# STUSB4500_PS.net
KiCad netlist of a schematic drawn in EAGLE
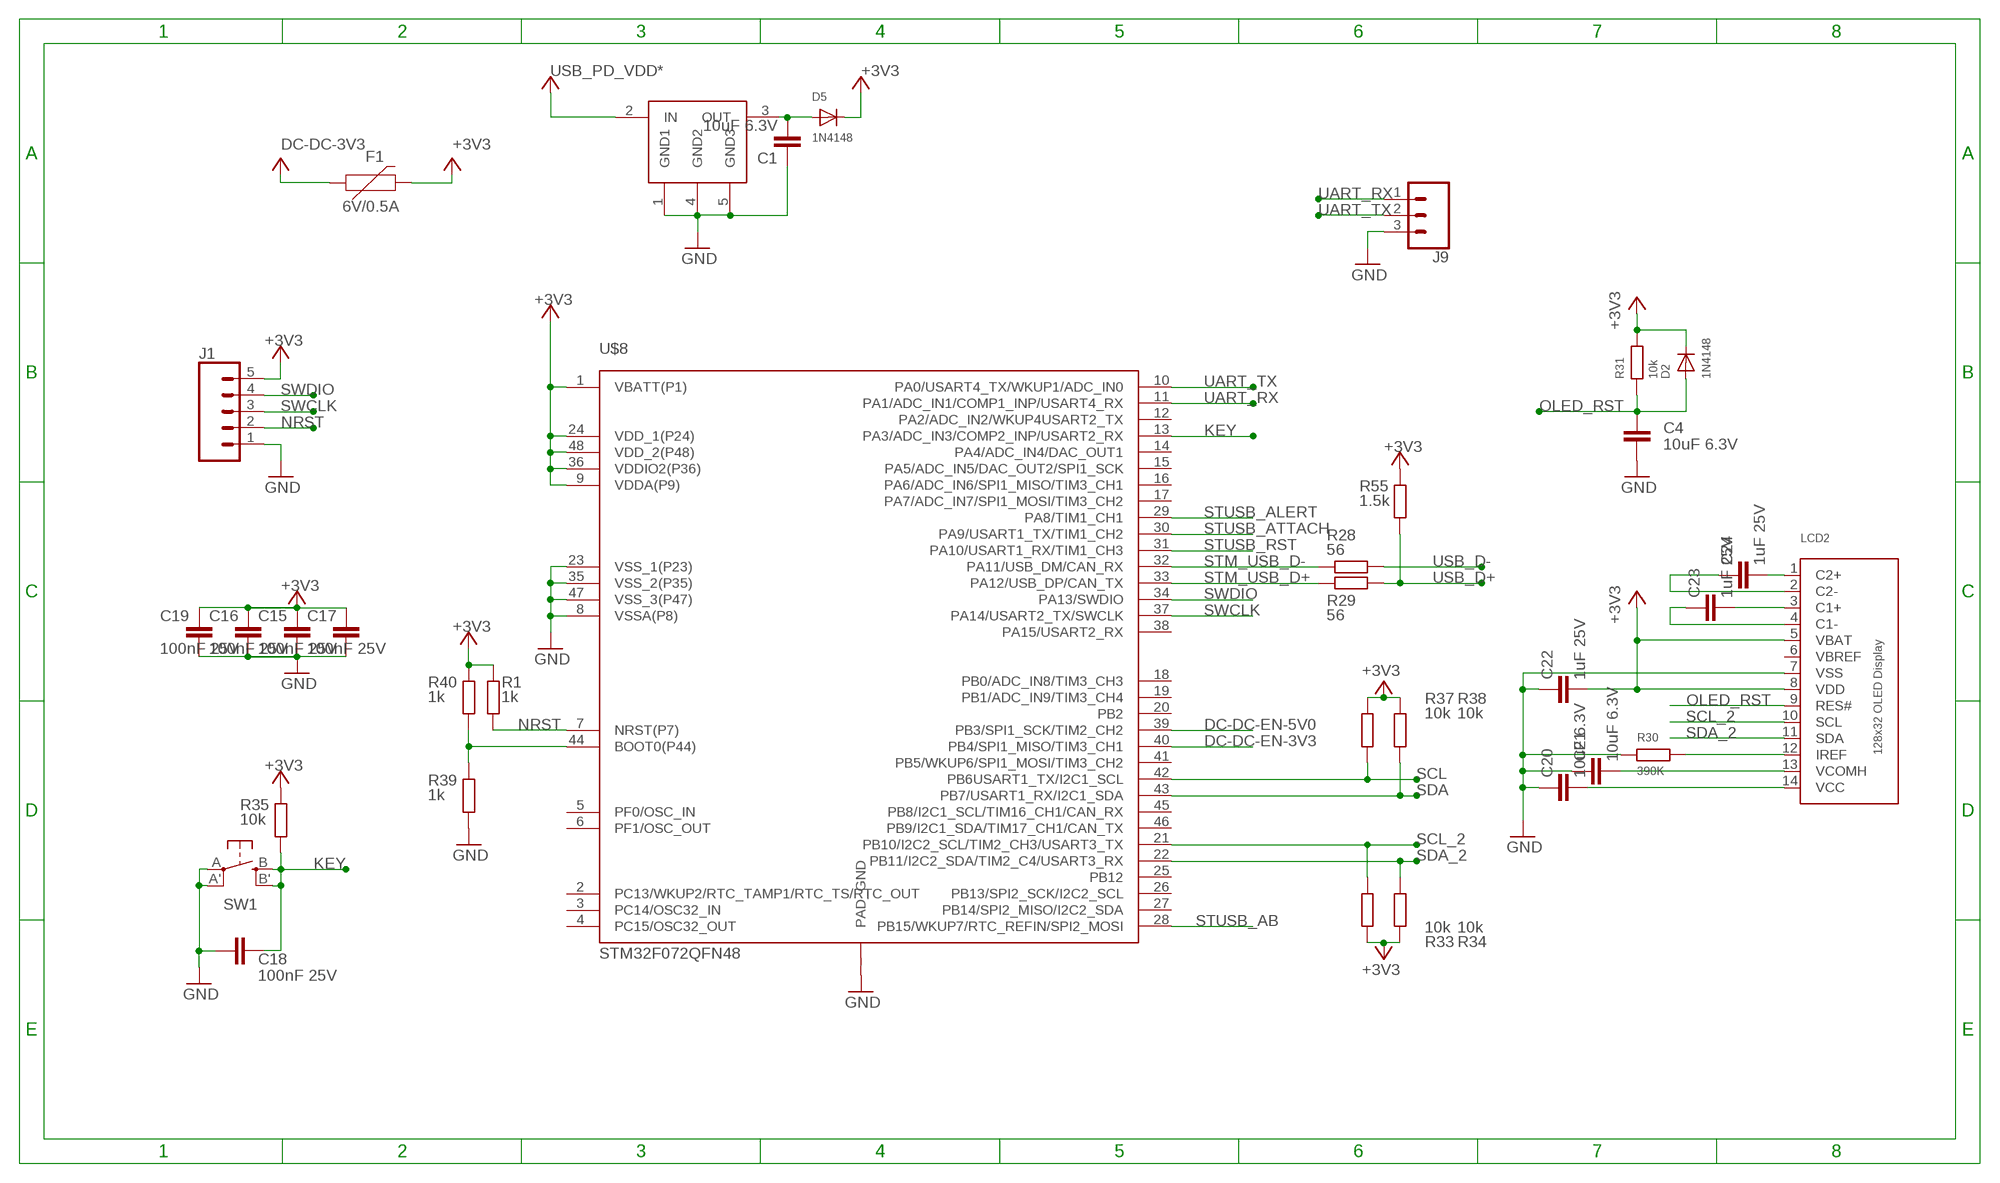
[diagram p0: schematic, sheet 1]
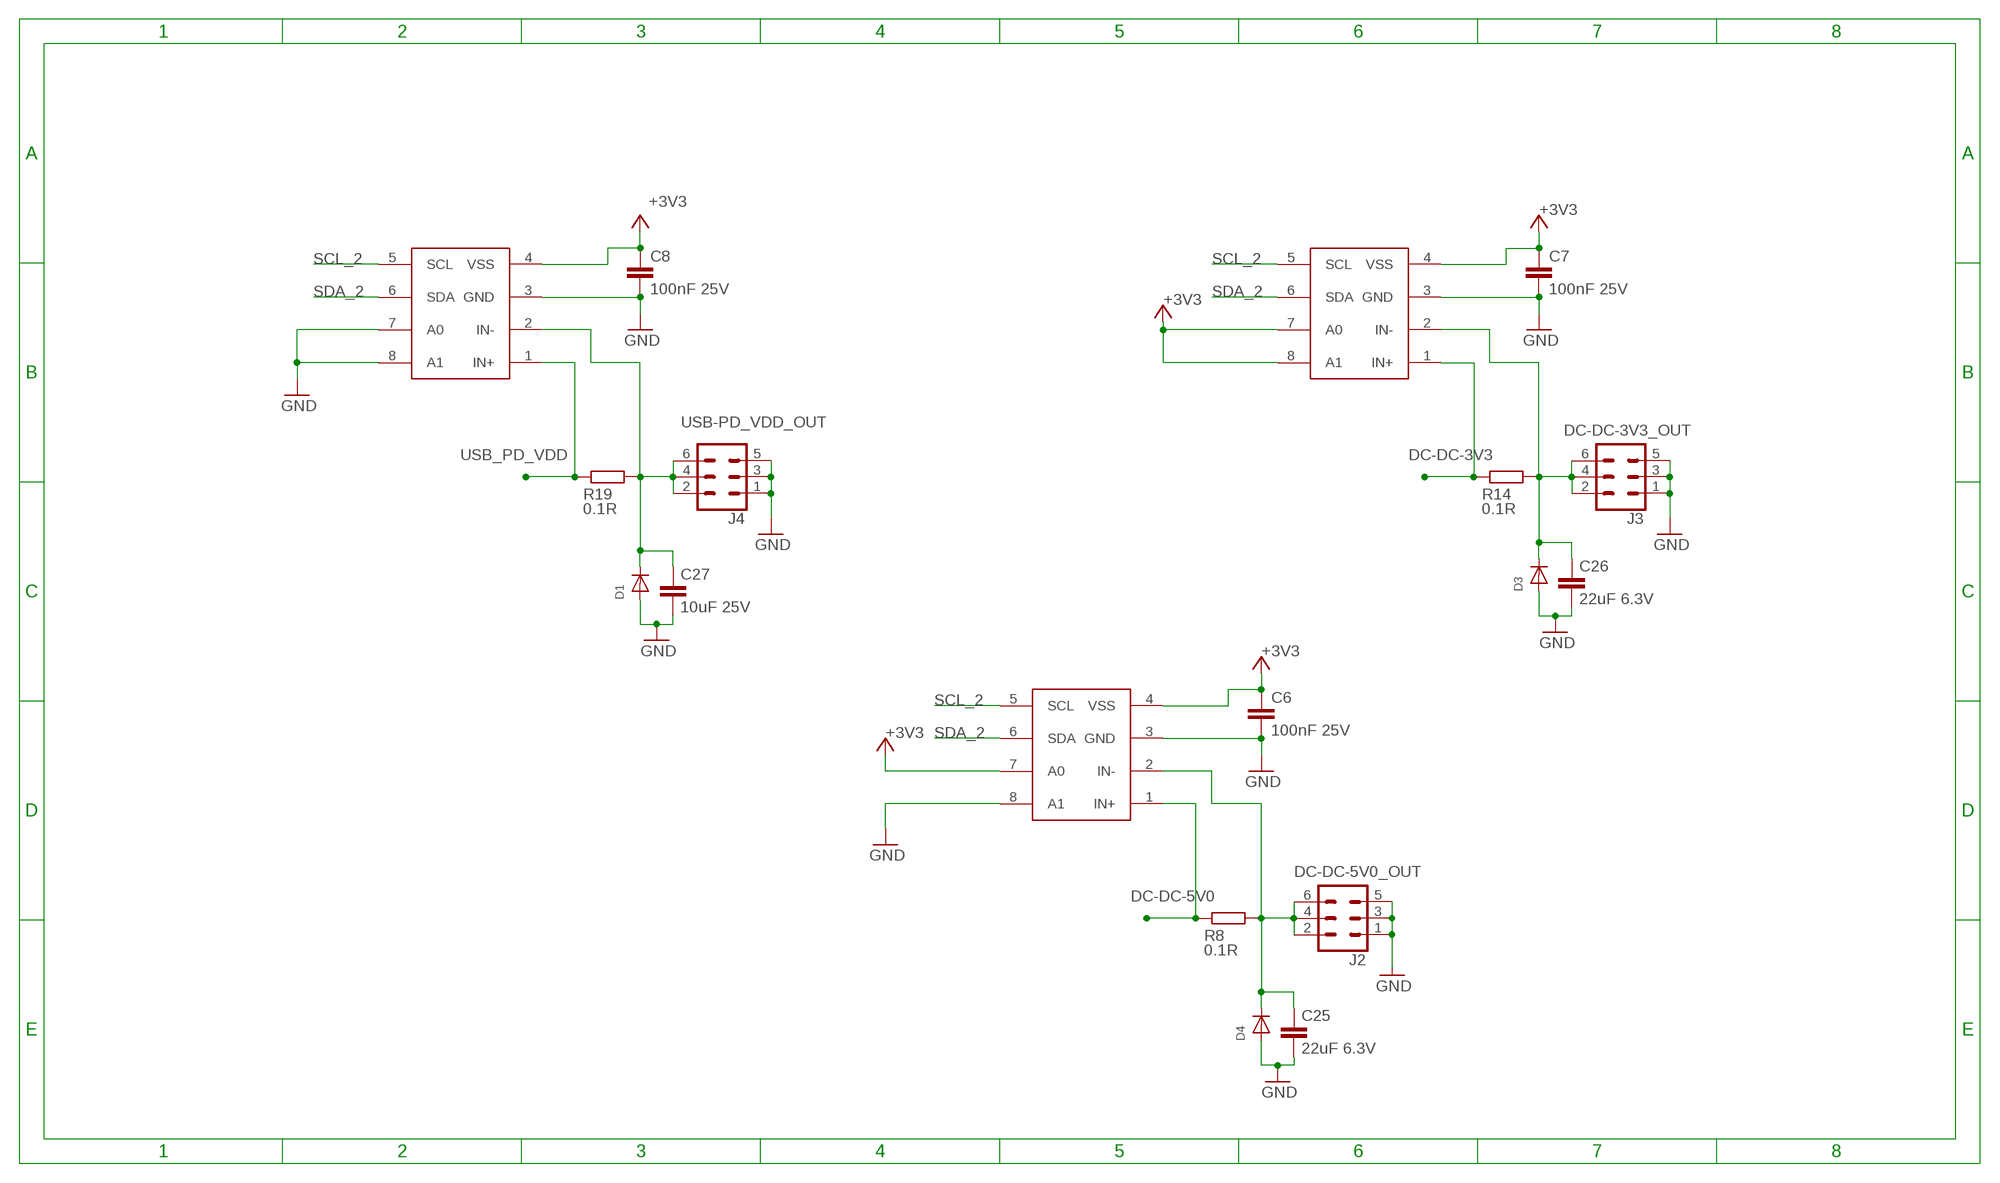
[diagram p1: schematic, sheet 2]
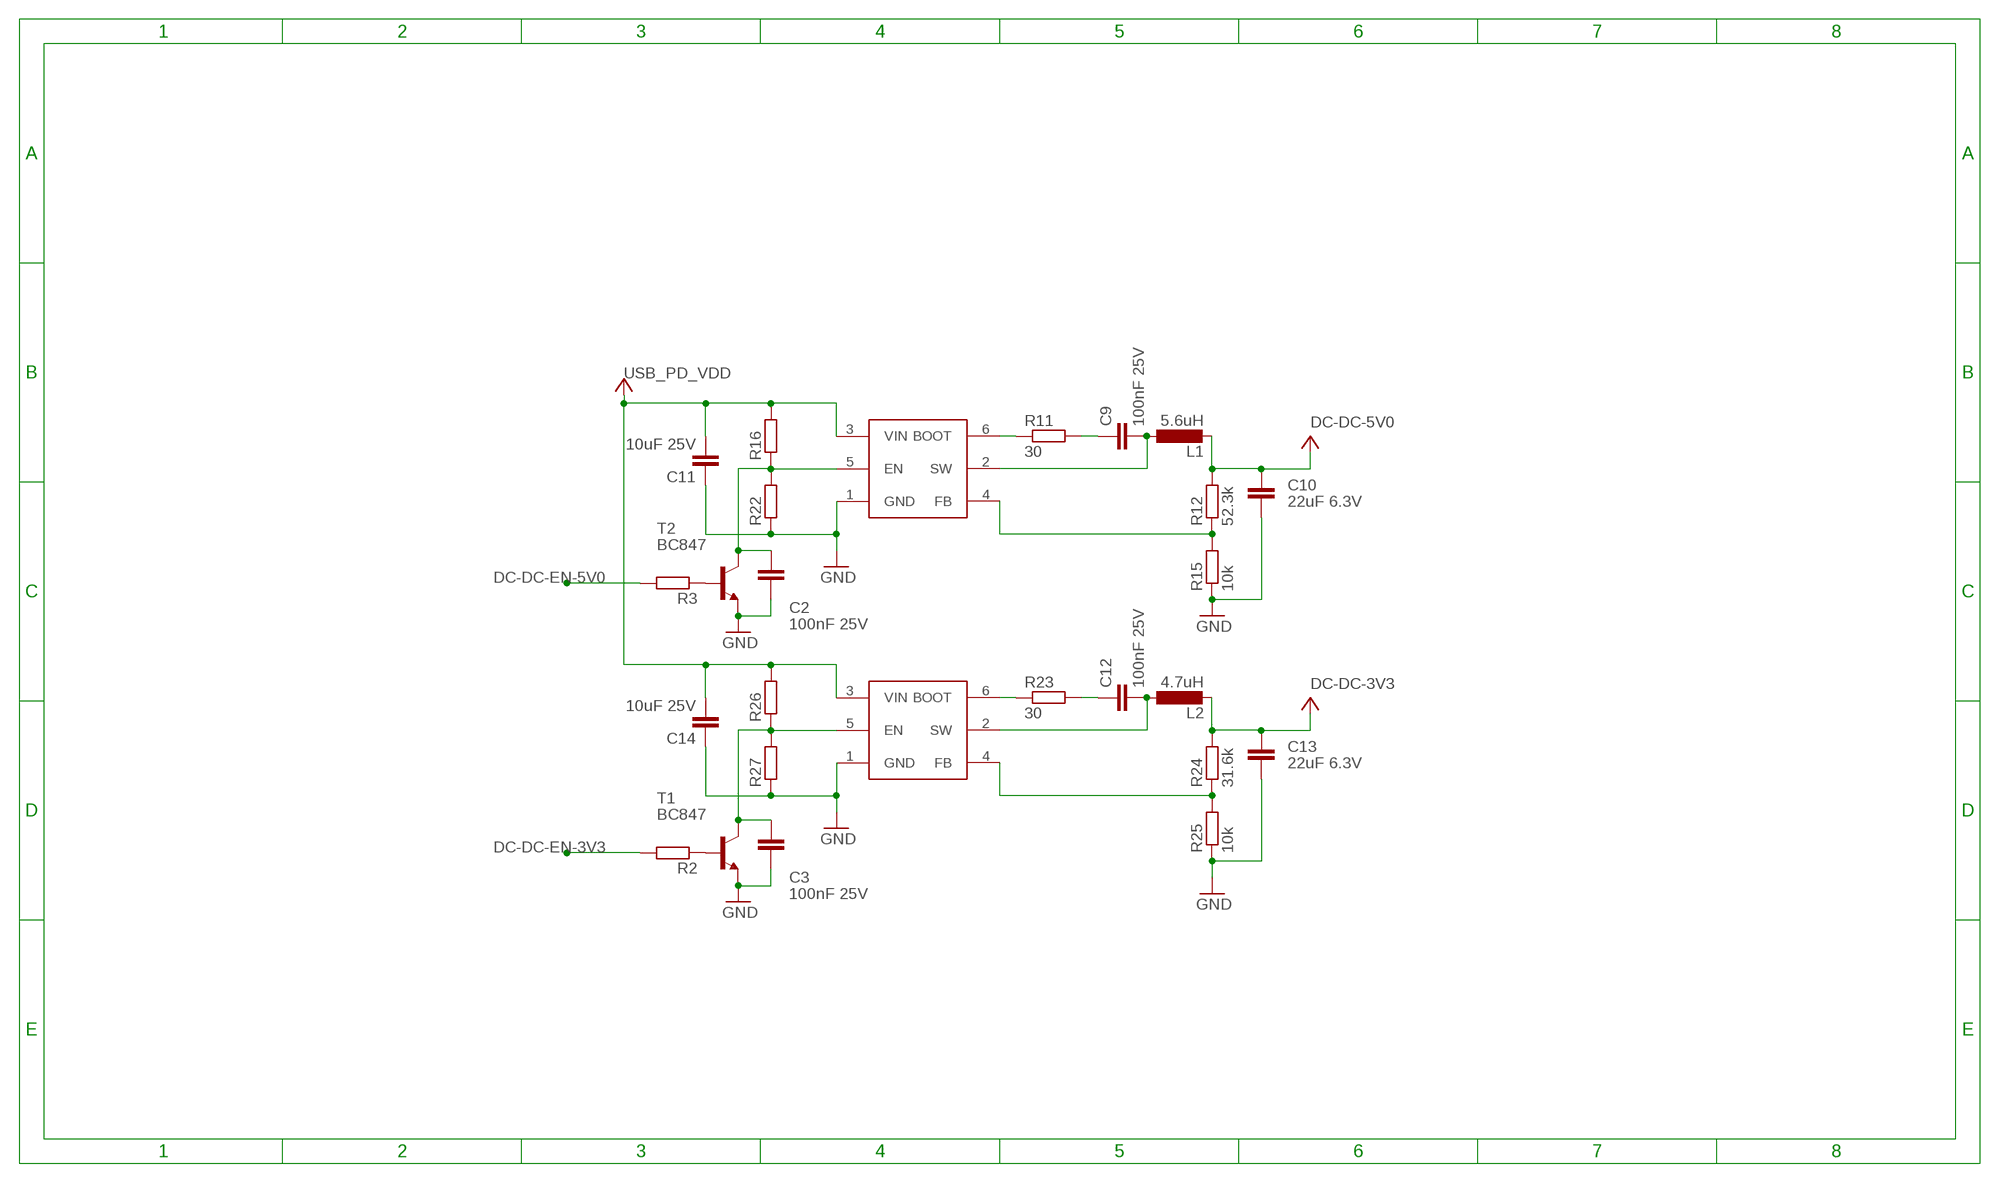
[diagram p2: schematic, sheet 3]
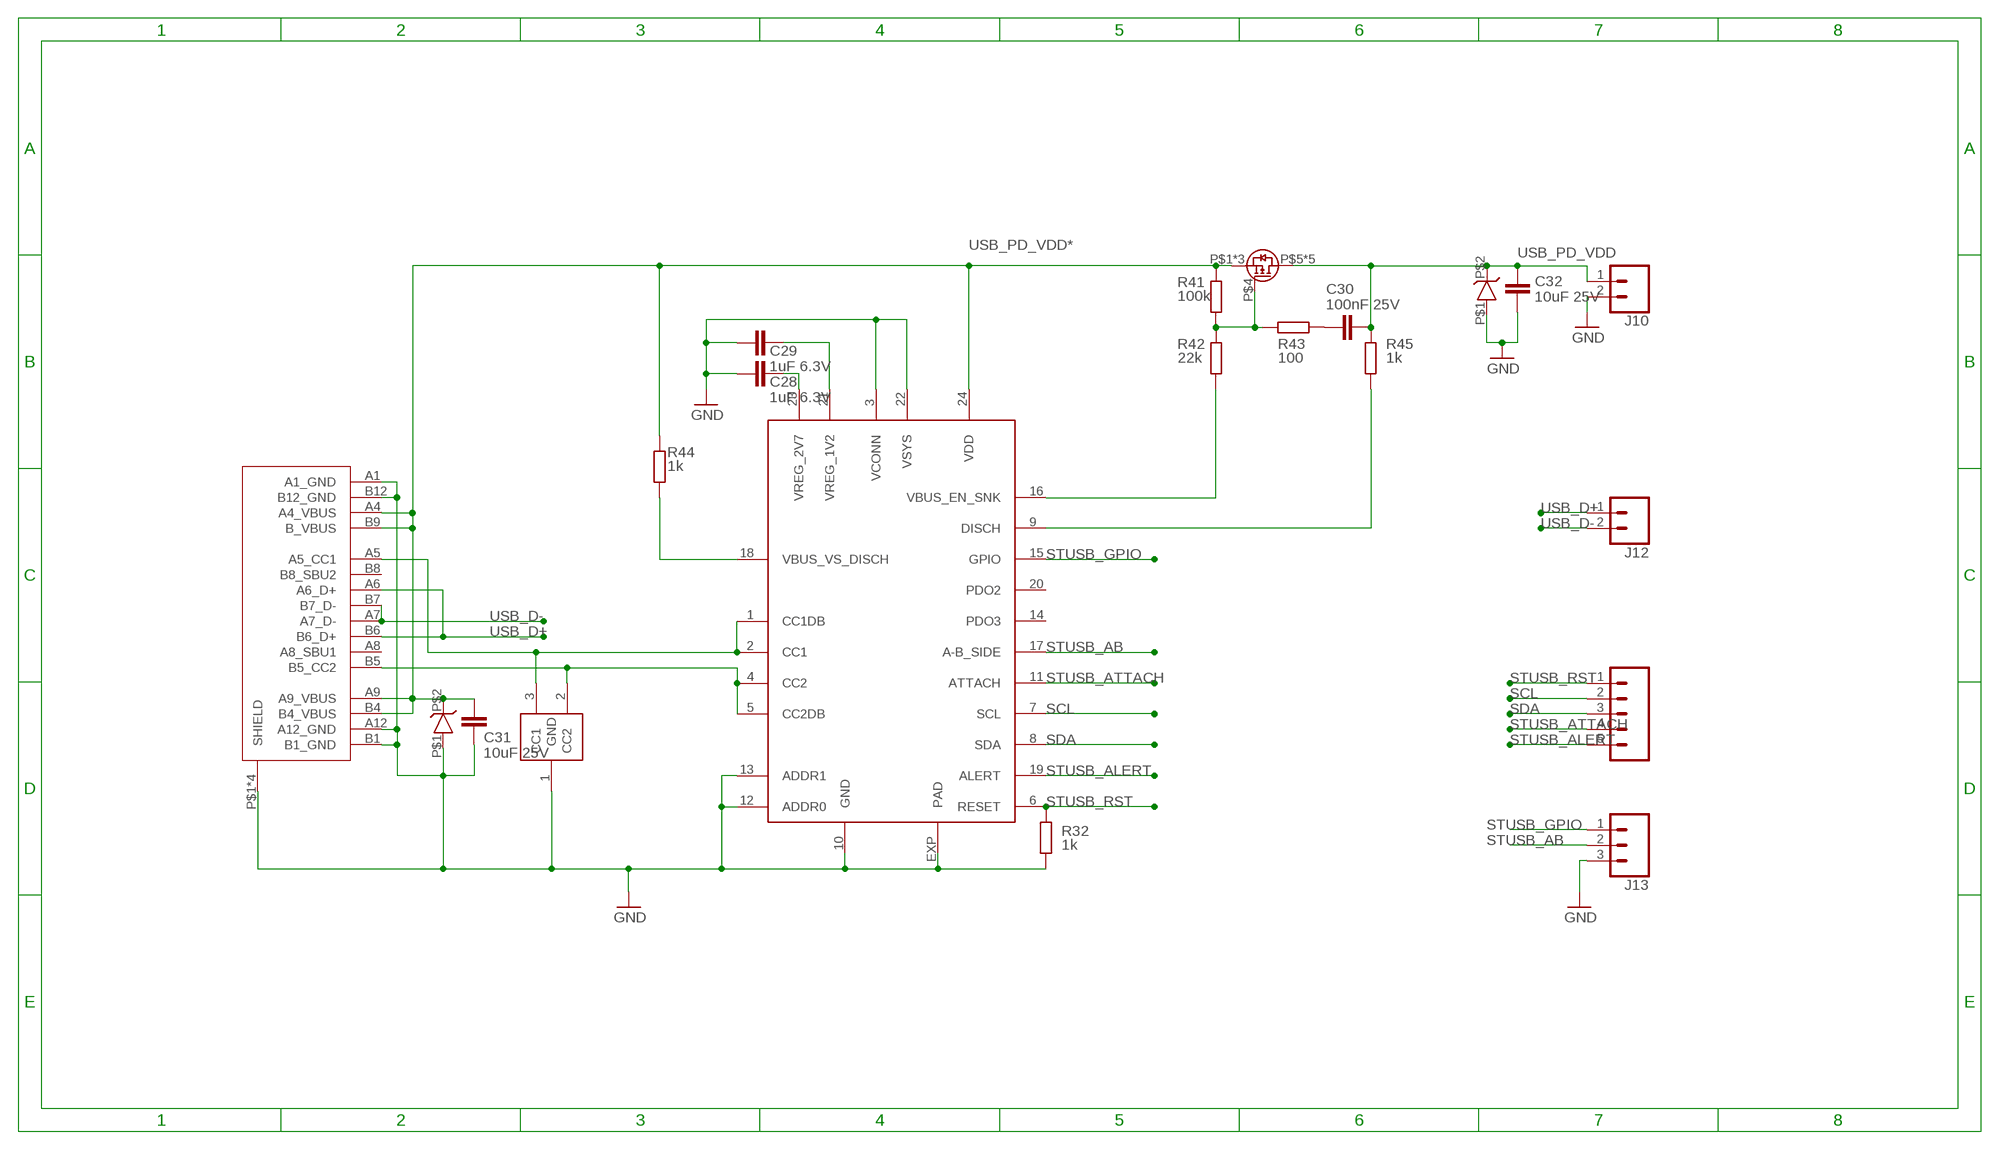
[diagram p3: schematic, sheet 4]

(export (version "E")
  (design (tool "Eeschema 10.0.6"))
  (components
    (comp (ref "C28")
      (value "1uF 6.3V")
      (footprint "eagle-import:C0402")
      (libsource (lib "eagle-import") (part "C-EUC0402"))
    )
    (comp (ref "C29")
      (value "1uF 6.3V")
      (footprint "eagle-import:C0402")
      (libsource (lib "eagle-import") (part "C-EUC0402"))
    )
    (comp (ref "C30")
      (value "100nF 25V")
      (footprint "eagle-import:C0402")
      (libsource (lib "eagle-import") (part "C-EUC0402"))
    )
    (comp (ref "C31")
      (value "10uF 25V")
      (footprint "eagle-import:C1206")
      (libsource (lib "eagle-import") (part "C-EUC1206"))
    )
    (comp (ref "C32")
      (value "10uF 25V")
      (footprint "eagle-import:C1206")
      (libsource (lib "eagle-import") (part "C-EUC1206"))
    )
    (comp (ref "ESDA25W1")
      (value "ESDA25WSOT323")
      (footprint "eagle-import:SOT323")
      (libsource (lib "eagle-import") (part "ESDA25WSOT323"))
    )
    (comp (ref "J10")
      (value "CONN_02LOCK")
      (footprint "eagle-import:1X02_LOCK")
      (libsource (lib "eagle-import") (part "CONN_02LOCK"))
    )
    (comp (ref "J11")
      (value "CONN_051.27MM")
      (footprint "eagle-import:1X05_1.27MM")
      (libsource (lib "eagle-import") (part "CONN_051.27MM"))
    )
    (comp (ref "J12")
      (value "CONN_021.27")
      (footprint "eagle-import:1X02_1.27MM")
      (libsource (lib "eagle-import") (part "CONN_021.27"))
    )
    (comp (ref "J13")
      (value "CONN_031.27")
      (footprint "eagle-import:1X03_1.27MM")
      (libsource (lib "eagle-import") (part "CONN_031.27"))
    )
    (comp (ref "R32")
      (value "1k")
      (footprint "eagle-import:R0402")
      (libsource (lib "eagle-import") (part "R-EU_R0402"))
    )
    (comp (ref "R41")
      (value "100k")
      (footprint "eagle-import:R0402")
      (libsource (lib "eagle-import") (part "R-EU_R0402"))
    )
    (comp (ref "R42")
      (value "22k")
      (footprint "eagle-import:R0402")
      (libsource (lib "eagle-import") (part "R-EU_R0402"))
    )
    (comp (ref "R43")
      (value "100")
      (footprint "eagle-import:R0402")
      (libsource (lib "eagle-import") (part "R-EU_R0402"))
    )
    (comp (ref "R44")
      (value "1k")
      (footprint "eagle-import:R0402")
      (libsource (lib "eagle-import") (part "R-EU_R0402"))
    )
    (comp (ref "R45")
      (value "1k")
      (footprint "eagle-import:R0402")
      (libsource (lib "eagle-import") (part "R-EU_R0402"))
    )
    (comp (ref "U$3")
      (value "STUSB4500QFN24_4X4")
      (footprint "eagle-import:QFN24-4X4")
      (libsource (lib "eagle-import") (part "STUSB4500QFN24_4X4"))
    )
    (comp (ref "U$13")
      (value "USB-C")
      (footprint "eagle-import:USB-C_16P")
      (libsource (lib "eagle-import") (part "USB-C"))
    )
    (comp (ref "U$14")
      (value "ESDA25P35")
      (footprint "eagle-import:1610")
      (libsource (lib "eagle-import") (part "ESDA25P35"))
    )
    (comp (ref "U$15")
      (value "ESDA25P35")
      (footprint "eagle-import:1610")
      (libsource (lib "eagle-import") (part "ESDA25P35"))
    )
    (comp (ref "U$16")
      (value "STL6P3LLH6")
      (footprint "eagle-import:POWER_FLAT_3X3")
      (libsource (lib "eagle-import") (part "STL6P3LLH6"))
    )
    (comp (ref "C2")
      (value "100nF 25V")
      (footprint "eagle-import:C0402")
      (libsource (lib "eagle-import") (part "C-EUC0402"))
    )
    (comp (ref "C3")
      (value "100nF 25V")
      (footprint "eagle-import:C0402")
      (libsource (lib "eagle-import") (part "C-EUC0402"))
    )
    (comp (ref "C9")
      (value "100nF 25V")
      (footprint "eagle-import:C0402")
      (libsource (lib "eagle-import") (part "C-EUC0402"))
    )
    (comp (ref "C10")
      (value "22uF 6.3V")
      (footprint "eagle-import:C1206")
      (libsource (lib "eagle-import") (part "C-EUC1206"))
    )
    (comp (ref "C11")
      (value "10uF 25V")
      (footprint "eagle-import:C1206")
      (libsource (lib "eagle-import") (part "C-EUC1206"))
    )
    (comp (ref "C12")
      (value "100nF 25V")
      (footprint "eagle-import:C0402")
      (libsource (lib "eagle-import") (part "C-EUC0402"))
    )
    (comp (ref "C13")
      (value "22uF 6.3V")
      (footprint "eagle-import:C1206")
      (libsource (lib "eagle-import") (part "C-EUC1206"))
    )
    (comp (ref "C14")
      (value "10uF 25V")
      (footprint "eagle-import:C1206")
      (libsource (lib "eagle-import") (part "C-EUC1206"))
    )
    (comp (ref "L1")
      (value "5.6uH")
      (footprint "eagle-import:POWER-CHOKE_WE-TPC")
      (libsource (lib "eagle-import") (part "L-EUWE-TPC"))
    )
    (comp (ref "L2")
      (value "4.7uH")
      (footprint "eagle-import:POWER-CHOKE_WE-TPC")
      (libsource (lib "eagle-import") (part "L-EUWE-TPC"))
    )
    (comp (ref "R2")
      (value "R-EU_R0402")
      (footprint "eagle-import:R0402")
      (libsource (lib "eagle-import") (part "R-EU_R0402"))
    )
    (comp (ref "R3")
      (value "R-EU_R0402")
      (footprint "eagle-import:R0402")
      (libsource (lib "eagle-import") (part "R-EU_R0402"))
    )
    (comp (ref "R11")
      (value "30")
      (footprint "eagle-import:R0402")
      (libsource (lib "eagle-import") (part "R-EU_R0402"))
    )
    (comp (ref "R12")
      (value "52.3k")
      (footprint "eagle-import:R0603")
      (libsource (lib "eagle-import") (part "R-EU_R0603"))
    )
    (comp (ref "R15")
      (value "10k")
      (footprint "eagle-import:R0603")
      (libsource (lib "eagle-import") (part "R-EU_R0603"))
    )
    (comp (ref "R16")
      (value "R-EU_R0402")
      (footprint "eagle-import:R0402")
      (libsource (lib "eagle-import") (part "R-EU_R0402"))
    )
    (comp (ref "R22")
      (value "R-EU_R0402")
      (footprint "eagle-import:R0402")
      (libsource (lib "eagle-import") (part "R-EU_R0402"))
    )
    (comp (ref "R23")
      (value "30")
      (footprint "eagle-import:R0402")
      (libsource (lib "eagle-import") (part "R-EU_R0402"))
    )
    (comp (ref "R24")
      (value "31.6k")
      (footprint "eagle-import:R0603")
      (libsource (lib "eagle-import") (part "R-EU_R0603"))
    )
    (comp (ref "R25")
      (value "10k")
      (footprint "eagle-import:R0603")
      (libsource (lib "eagle-import") (part "R-EU_R0603"))
    )
    (comp (ref "R26")
      (value "R-EU_R0402")
      (footprint "eagle-import:R0402")
      (libsource (lib "eagle-import") (part "R-EU_R0402"))
    )
    (comp (ref "R27")
      (value "R-EU_R0402")
      (footprint "eagle-import:R0402")
      (libsource (lib "eagle-import") (part "R-EU_R0402"))
    )
    (comp (ref "T1")
      (value "BC847")
      (footprint "eagle-import:SOT23")
      (libsource (lib "eagle-import") (part "BC847"))
    )
    (comp (ref "T2")
      (value "BC847")
      (footprint "eagle-import:SOT23")
      (libsource (lib "eagle-import") (part "BC847"))
    )
    (comp (ref "U$11")
      (value "TPS56339SOT23-6")
      (footprint "eagle-import:TEXAS_SOT23-6")
      (libsource (lib "eagle-import") (part "TPS56339SOT23-6"))
    )
    (comp (ref "U$12")
      (value "TPS56339SOT23-6")
      (footprint "eagle-import:TEXAS_SOT23-6")
      (libsource (lib "eagle-import") (part "TPS56339SOT23-6"))
    )
    (comp (ref "C1")
      (value "10uF 6.3V")
      (footprint "eagle-import:C0603")
      (libsource (lib "eagle-import") (part "C-EUC0603"))
    )
    (comp (ref "C4")
      (value "10uF 6.3V")
      (footprint "eagle-import:C0603")
      (libsource (lib "eagle-import") (part "C-EUC0603"))
    )
    (comp (ref "C15")
      (value "100nF 25V")
      (footprint "eagle-import:C0402")
      (libsource (lib "eagle-import") (part "C-EUC0402"))
    )
    (comp (ref "C16")
      (value "100nF 25V")
      (footprint "eagle-import:C0402")
      (libsource (lib "eagle-import") (part "C-EUC0402"))
    )
    (comp (ref "C17")
      (value "100nF 25V")
      (footprint "eagle-import:C0402")
      (libsource (lib "eagle-import") (part "C-EUC0402"))
    )
    (comp (ref "C18")
      (value "100nF 25V")
      (footprint "eagle-import:C0402")
      (libsource (lib "eagle-import") (part "C-EUC0402"))
    )
    (comp (ref "C19")
      (value "100nF 25V")
      (footprint "eagle-import:C0402")
      (libsource (lib "eagle-import") (part "C-EUC0402"))
    )
    (comp (ref "C20")
      (value "10uF 6.3V")
      (footprint "eagle-import:C0603")
      (libsource (lib "eagle-import") (part "C-EUC0603"))
    )
    (comp (ref "C21")
      (value "10uF 6.3V")
      (footprint "eagle-import:C0603")
      (libsource (lib "eagle-import") (part "C-EUC0603"))
    )
    (comp (ref "C22")
      (value "1uF 25V")
      (footprint "eagle-import:C0603")
      (libsource (lib "eagle-import") (part "C-EUC0603"))
    )
    (comp (ref "C23")
      (value "1uF 25V")
      (footprint "eagle-import:C0603")
      (libsource (lib "eagle-import") (part "C-EUC0603"))
    )
    (comp (ref "C24")
      (value "1uF 25V")
      (footprint "eagle-import:C0603")
      (libsource (lib "eagle-import") (part "C-EUC0603"))
    )
    (comp (ref "D2")
      (value "1N4148")
      (footprint "eagle-import:SOD-323F")
      (libsource (lib "eagle-import") (part "DIODESOD-323F"))
    )
    (comp (ref "D5")
      (value "1N4148")
      (footprint "eagle-import:SOD-323F")
      (libsource (lib "eagle-import") (part "DIODESOD-323F"))
    )
    (comp (ref "F1")
      (value "6V/0.5A")
      (footprint "eagle-import:1206")
      (libsource (lib "eagle-import") (part "PPTC_HALF-AMP"))
    )
    (comp (ref "J1")
      (value "CONN_05LOCK")
      (footprint "eagle-import:1X05_LOCK")
      (libsource (lib "eagle-import") (part "CONN_05LOCK"))
    )
    (comp (ref "J9")
      (value "CONN_03LOCK_NO_SILK")
      (footprint "eagle-import:1X03_LOCK_NO_SILK")
      (libsource (lib "eagle-import") (part "CONN_03LOCK_NO_SILK"))
    )
    (comp (ref "LCD2")
      (value "DISP_OLED_UG-2832HSWEG02")
      (footprint "eagle-import:UG-2832HSWEG02_WRAPUNDER")
      (libsource (lib "eagle-import") (part "DISP_OLED_UG-2832HSWEG02"))
    )
    (comp (ref "R1")
      (value "1k")
      (footprint "eagle-import:R0402")
      (libsource (lib "eagle-import") (part "R-EU_R0402"))
    )
    (comp (ref "R28")
      (value "56")
      (footprint "eagle-import:R0402")
      (libsource (lib "eagle-import") (part "R-EU_R0402"))
    )
    (comp (ref "R29")
      (value "56")
      (footprint "eagle-import:R0402")
      (libsource (lib "eagle-import") (part "R-EU_R0402"))
    )
    (comp (ref "R30")
      (value "390K")
      (footprint "eagle-import:R0603")
      (libsource (lib "eagle-import") (part "R-EU_R0603"))
    )
    (comp (ref "R31")
      (value "10k")
      (footprint "eagle-import:R0603")
      (libsource (lib "eagle-import") (part "R-EU_R0603"))
    )
    (comp (ref "R33")
      (value "10k")
      (footprint "eagle-import:R0402")
      (libsource (lib "eagle-import") (part "R-EU_R0402"))
    )
    (comp (ref "R34")
      (value "10k")
      (footprint "eagle-import:R0402")
      (libsource (lib "eagle-import") (part "R-EU_R0402"))
    )
    (comp (ref "R35")
      (value "10k")
      (footprint "eagle-import:R0402")
      (libsource (lib "eagle-import") (part "R-EU_R0402"))
    )
    (comp (ref "R37")
      (value "10k")
      (footprint "eagle-import:R0402")
      (libsource (lib "eagle-import") (part "R-EU_R0402"))
    )
    (comp (ref "R38")
      (value "10k")
      (footprint "eagle-import:R0402")
      (libsource (lib "eagle-import") (part "R-EU_R0402"))
    )
    (comp (ref "R39")
      (value "1k")
      (footprint "eagle-import:R0402")
      (libsource (lib "eagle-import") (part "R-EU_R0402"))
    )
    (comp (ref "R40")
      (value "1k")
      (footprint "eagle-import:R0402")
      (libsource (lib "eagle-import") (part "R-EU_R0402"))
    )
    (comp (ref "R55")
      (value "1.5k")
      (footprint "eagle-import:R0402")
      (libsource (lib "eagle-import") (part "R-EU_R0402"))
    )
    (comp (ref "SW1")
      (value "SPST_TACT-EVQQ2")
      (footprint "eagle-import:EVQ-Q2")
      (libsource (lib "eagle-import") (part "SPST_TACT-EVQQ2"))
    )
    (comp (ref "U$1")
      (value "TLV704_3V3SOT23-5")
      (footprint "eagle-import:SOT23-5")
      (libsource (lib "eagle-import") (part "TLV704_3V3SOT23-5"))
    )
    (comp (ref "U$8")
      (value "STM32F072QFN48")
      (footprint "eagle-import:P-HVQFN48-7X7")
      (libsource (lib "eagle-import") (part "STM32F072QFN48"))
    )
    (comp (ref "C6")
      (value "100nF 25V")
      (footprint "eagle-import:C0402")
      (libsource (lib "eagle-import") (part "C-EUC0402"))
    )
    (comp (ref "C7")
      (value "100nF 25V")
      (footprint "eagle-import:C0402")
      (libsource (lib "eagle-import") (part "C-EUC0402"))
    )
    (comp (ref "C8")
      (value "100nF 25V")
      (footprint "eagle-import:C0402")
      (libsource (lib "eagle-import") (part "C-EUC0402"))
    )
    (comp (ref "C25")
      (value "22uF 6.3V")
      (footprint "eagle-import:C1206")
      (libsource (lib "eagle-import") (part "C-EUC1206"))
    )
    (comp (ref "C26")
      (value "22uF 6.3V")
      (footprint "eagle-import:C1206")
      (libsource (lib "eagle-import") (part "C-EUC1206"))
    )
    (comp (ref "C27")
      (value "10uF 25V")
      (footprint "eagle-import:C1206")
      (libsource (lib "eagle-import") (part "C-EUC1206"))
    )
    (comp (ref "D1")
      (value "DIODE_SOD-123FL")
      (footprint "eagle-import:SOD-123FL")
      (libsource (lib "eagle-import") (part "DIODE_SOD-123FL"))
    )
    (comp (ref "D3")
      (value "DIODE_SOD-123FL")
      (footprint "eagle-import:SOD-123FL")
      (libsource (lib "eagle-import") (part "DIODE_SOD-123FL"))
    )
    (comp (ref "D4")
      (value "DIODE_SOD-123FL")
      (footprint "eagle-import:SOD-123FL")
      (libsource (lib "eagle-import") (part "DIODE_SOD-123FL"))
    )
    (comp (ref "J2")
      (value "FEMALE 2x3")
      (footprint "eagle-import:2X3-NS")
      (libsource (lib "eagle-import") (part "CONN_03X2NO_SILK"))
    )
    (comp (ref "J3")
      (value "FEMALE 2x3")
      (footprint "eagle-import:2X3-NS")
      (libsource (lib "eagle-import") (part "CONN_03X2NO_SILK"))
    )
    (comp (ref "J4")
      (value "FEMALE 2x3")
      (footprint "eagle-import:2X3-NS")
      (libsource (lib "eagle-import") (part "CONN_03X2NO_SILK"))
    )
    (comp (ref "R8")
      (value "0.1R")
      (footprint "eagle-import:R2010")
      (libsource (lib "eagle-import") (part "R-EU_R2010"))
    )
    (comp (ref "R14")
      (value "0.1R")
      (footprint "eagle-import:R2010")
      (libsource (lib "eagle-import") (part "R-EU_R2010"))
    )
    (comp (ref "R19")
      (value "0.1R")
      (footprint "eagle-import:R2010")
      (libsource (lib "eagle-import") (part "R-EU_R2010"))
    )
    (comp (ref "U$7")
      (value "INA219DCN")
      (footprint "eagle-import:DCN-R-PDSO-G8")
      (libsource (lib "eagle-import") (part "INA219DCN"))
    )
    (comp (ref "U$9")
      (value "INA219DCN")
      (footprint "eagle-import:DCN-R-PDSO-G8")
      (libsource (lib "eagle-import") (part "INA219DCN"))
    )
    (comp (ref "U$10")
      (value "INA219DCN")
      (footprint "eagle-import:DCN-R-PDSO-G8")
      (libsource (lib "eagle-import") (part "INA219DCN"))
    )
  )
  (nets
    (net (code "1") (name "+3V3") (class "Default")
      (node (ref "C15") (pin "1") (pinfunction "1_1") (pintype "passive"))
      (node (ref "C16") (pin "1") (pinfunction "1_1") (pintype "passive"))
      (node (ref "C17") (pin "1") (pinfunction "1_1") (pintype "passive"))
      (node (ref "C19") (pin "1") (pinfunction "1_1") (pintype "passive"))
      (node (ref "C22") (pin "2") (pinfunction "2_2") (pintype "passive"))
      (node (ref "C6") (pin "1") (pinfunction "1_1") (pintype "passive"))
      (node (ref "C7") (pin "1") (pinfunction "1_1") (pintype "passive"))
      (node (ref "C8") (pin "1") (pinfunction "1_1") (pintype "passive"))
      (node (ref "D2") (pin "C") (pinfunction "C_C") (pintype "passive"))
      (node (ref "D5") (pin "C") (pinfunction "C_C") (pintype "passive"))
      (node (ref "F1") (pin "2") (pinfunction "2_2") (pintype "bidirectional"))
      (node (ref "J1") (pin "5") (pinfunction "5_5") (pintype "passive"))
      (node (ref "LCD2") (pin "5") (pinfunction "VBAT_5") (pintype "power_in"))
      (node (ref "LCD2") (pin "8") (pinfunction "VDD_8") (pintype "power_in"))
      (node (ref "R1") (pin "2") (pinfunction "2_2") (pintype "passive"))
      (node (ref "R31") (pin "2") (pinfunction "2_2") (pintype "passive"))
      (node (ref "R33") (pin "2") (pinfunction "2_2") (pintype "passive"))
      (node (ref "R34") (pin "2") (pinfunction "2_2") (pintype "passive"))
      (node (ref "R35") (pin "2") (pinfunction "2_2") (pintype "passive"))
      (node (ref "R37") (pin "2") (pinfunction "2_2") (pintype "passive"))
      (node (ref "R38") (pin "2") (pinfunction "2_2") (pintype "passive"))
      (node (ref "R40") (pin "2") (pinfunction "2_2") (pintype "passive"))
      (node (ref "R55") (pin "2") (pinfunction "2_2") (pintype "passive"))
      (node (ref "U$10") (pin "4") (pinfunction "VSS_4") (pintype "bidirectional"))
      (node (ref "U$7") (pin "4") (pinfunction "VSS_4") (pintype "bidirectional"))
      (node (ref "U$7") (pin "7") (pinfunction "A0_7") (pintype "bidirectional"))
      (node (ref "U$8") (pin "1") (pinfunction "VBATT(P1)_1") (pintype "bidirectional"))
      (node (ref "U$8") (pin "24") (pinfunction "VDD_1(P24)_24") (pintype "bidirectional"))
      (node (ref "U$8") (pin "36") (pinfunction "VDDIO2(P36)_36") (pintype "bidirectional"))
      (node (ref "U$8") (pin "48") (pinfunction "VDD_2(P48)_48") (pintype "bidirectional"))
      (node (ref "U$8") (pin "9") (pinfunction "VDDA(P9)_9") (pintype "bidirectional"))
      (node (ref "U$9") (pin "4") (pinfunction "VSS_4") (pintype "bidirectional"))
      (node (ref "U$9") (pin "7") (pinfunction "A0_7") (pintype "bidirectional"))
      (node (ref "U$9") (pin "8") (pinfunction "A1_8") (pintype "bidirectional"))
    )
    (net (code "2") (name "DC-DC-3V3") (class "Default")
      (node (ref "C13") (pin "2") (pinfunction "2_2") (pintype "passive"))
      (node (ref "F1") (pin "1") (pinfunction "1_1") (pintype "bidirectional"))
      (node (ref "L2") (pin "2") (pinfunction "2_2") (pintype "passive"))
      (node (ref "R14") (pin "2") (pinfunction "2_2") (pintype "passive"))
      (node (ref "R24") (pin "2") (pinfunction "2_2") (pintype "passive"))
      (node (ref "U$9") (pin "1") (pinfunction "IN+_1") (pintype "bidirectional"))
    )
    (net (code "3") (name "DC-DC-3V3_OUT") (class "Default")
      (node (ref "C26") (pin "1") (pinfunction "1_1") (pintype "passive"))
      (node (ref "D3") (pin "C") (pinfunction "C_C") (pintype "passive"))
      (node (ref "J3") (pin "2") (pinfunction "2_2") (pintype "bidirectional"))
      (node (ref "J3") (pin "4") (pinfunction "4_4") (pintype "bidirectional"))
      (node (ref "J3") (pin "6") (pinfunction "6_6") (pintype "bidirectional"))
      (node (ref "R14") (pin "1") (pinfunction "1_1") (pintype "passive"))
      (node (ref "U$9") (pin "2") (pinfunction "IN-_2") (pintype "bidirectional"))
    )
    (net (code "4") (name "DC-DC-5V0") (class "Default")
      (node (ref "C10") (pin "2") (pinfunction "2_2") (pintype "passive"))
      (node (ref "L1") (pin "2") (pinfunction "2_2") (pintype "passive"))
      (node (ref "R12") (pin "2") (pinfunction "2_2") (pintype "passive"))
      (node (ref "R8") (pin "2") (pinfunction "2_2") (pintype "passive"))
      (node (ref "U$7") (pin "1") (pinfunction "IN+_1") (pintype "bidirectional"))
    )
    (net (code "5") (name "DC-DC-5V0_OUT") (class "Default")
      (node (ref "C25") (pin "1") (pinfunction "1_1") (pintype "passive"))
      (node (ref "D4") (pin "C") (pinfunction "C_C") (pintype "passive"))
      (node (ref "J2") (pin "2") (pinfunction "2_2") (pintype "bidirectional"))
      (node (ref "J2") (pin "4") (pinfunction "4_4") (pintype "bidirectional"))
      (node (ref "J2") (pin "6") (pinfunction "6_6") (pintype "bidirectional"))
      (node (ref "R8") (pin "1") (pinfunction "1_1") (pintype "passive"))
      (node (ref "U$7") (pin "2") (pinfunction "IN-_2") (pintype "bidirectional"))
    )
    (net (code "6") (name "DC-DC-EN-3V3") (class "Default")
      (node (ref "R2") (pin "2") (pinfunction "2_2") (pintype "passive"))
      (node (ref "U$8") (pin "40") (pinfunction "PB4/SPI1_MISO/TIM3_CH1_40") (pintype "bidirectional"))
    )
    (net (code "7") (name "DC-DC-EN-5V0") (class "Default")
      (node (ref "R3") (pin "2") (pinfunction "2_2") (pintype "passive"))
      (node (ref "U$8") (pin "39") (pinfunction "PB3/SPI1_SCK/TIM2_CH2_39") (pintype "bidirectional"))
    )
    (net (code "8") (name "GND") (class "Default")
      (node (ref "C1") (pin "1") (pinfunction "1_1") (pintype "passive"))
      (node (ref "C10") (pin "1") (pinfunction "1_1") (pintype "passive"))
      (node (ref "C11") (pin "1") (pinfunction "1_1") (pintype "passive"))
      (node (ref "C13") (pin "1") (pinfunction "1_1") (pintype "passive"))
      (node (ref "C14") (pin "1") (pinfunction "1_1") (pintype "passive"))
      (node (ref "C15") (pin "2") (pinfunction "2_2") (pintype "passive"))
      (node (ref "C16") (pin "2") (pinfunction "2_2") (pintype "passive"))
      (node (ref "C17") (pin "2") (pinfunction "2_2") (pintype "passive"))
      (node (ref "C18") (pin "1") (pinfunction "1_1") (pintype "passive"))
      (node (ref "C19") (pin "2") (pinfunction "2_2") (pintype "passive"))
      (node (ref "C2") (pin "1") (pinfunction "1_1") (pintype "passive"))
      (node (ref "C20") (pin "1") (pinfunction "1_1") (pintype "passive"))
      (node (ref "C21") (pin "1") (pinfunction "1_1") (pintype "passive"))
      (node (ref "C22") (pin "1") (pinfunction "1_1") (pintype "passive"))
      (node (ref "C25") (pin "2") (pinfunction "2_2") (pintype "passive"))
      (node (ref "C26") (pin "2") (pinfunction "2_2") (pintype "passive"))
      (node (ref "C27") (pin "2") (pinfunction "2_2") (pintype "passive"))
      (node (ref "C28") (pin "2") (pinfunction "2_2") (pintype "passive"))
      (node (ref "C29") (pin "2") (pinfunction "2_2") (pintype "passive"))
      (node (ref "C3") (pin "1") (pinfunction "1_1") (pintype "passive"))
      (node (ref "C31") (pin "2") (pinfunction "2_2") (pintype "passive"))
      (node (ref "C32") (pin "2") (pinfunction "2_2") (pintype "passive"))
      (node (ref "C4") (pin "1") (pinfunction "1_1") (pintype "passive"))
      (node (ref "C6") (pin "2") (pinfunction "2_2") (pintype "passive"))
      (node (ref "C7") (pin "2") (pinfunction "2_2") (pintype "passive"))
      (node (ref "C8") (pin "2") (pinfunction "2_2") (pintype "passive"))
      (node (ref "D1") (pin "A") (pinfunction "A_A") (pintype "passive"))
      (node (ref "D3") (pin "A") (pinfunction "A_A") (pintype "passive"))
      (node (ref "D4") (pin "A") (pinfunction "A_A") (pintype "passive"))
      (node (ref "ESDA25W1") (pin "1") (pinfunction "GND_1") (pintype "bidirectional"))
      (node (ref "J1") (pin "1") (pinfunction "1_1") (pintype "passive"))
      (node (ref "J10") (pin "2") (pinfunction "2_2") (pintype "passive"))
      (node (ref "J13") (pin "3") (pinfunction "3_3") (pintype "passive"))
      (node (ref "J2") (pin "1") (pinfunction "1_1") (pintype "bidirectional"))
      (node (ref "J2") (pin "3") (pinfunction "3_3") (pintype "bidirectional"))
      (node (ref "J2") (pin "5") (pinfunction "5_5") (pintype "bidirectional"))
      (node (ref "J3") (pin "1") (pinfunction "1_1") (pintype "bidirectional"))
      (node (ref "J3") (pin "3") (pinfunction "3_3") (pintype "bidirectional"))
      (node (ref "J3") (pin "5") (pinfunction "5_5") (pintype "bidirectional"))
      (node (ref "J4") (pin "1") (pinfunction "1_1") (pintype "bidirectional"))
      (node (ref "J4") (pin "3") (pinfunction "3_3") (pintype "bidirectional"))
      (node (ref "J4") (pin "5") (pinfunction "5_5") (pintype "bidirectional"))
      (node (ref "J9") (pin "3") (pinfunction "3_3") (pintype "passive"))
      (node (ref "LCD2") (pin "7") (pinfunction "VSS_7") (pintype "power_in"))
      (node (ref "R15") (pin "1") (pinfunction "1_1") (pintype "passive"))
      (node (ref "R22") (pin "1") (pinfunction "1_1") (pintype "passive"))
      (node (ref "R25") (pin "1") (pinfunction "1_1") (pintype "passive"))
      (node (ref "R27") (pin "1") (pinfunction "1_1") (pintype "passive"))
      (node (ref "R30") (pin "1") (pinfunction "1_1") (pintype "passive"))
      (node (ref "R32") (pin "1") (pinfunction "1_1") (pintype "passive"))
      (node (ref "R39") (pin "1") (pinfunction "1_1") (pintype "passive"))
      (node (ref "SW1") (pin "A") (pinfunction "P_A") (pintype "passive"))
      (node (ref "SW1") (pin "A'") (pinfunction "P1_A'") (pintype "passive"))
      (node (ref "T1") (pin "2") (pinfunction "E_2") (pintype "passive"))
      (node (ref "T2") (pin "2") (pinfunction "E_2") (pintype "passive"))
      (node (ref "U$1") (pin "1") (pinfunction "GND1_1") (pintype "bidirectional"))
      (node (ref "U$1") (pin "4") (pinfunction "GND2_4") (pintype "bidirectional"))
      (node (ref "U$1") (pin "5") (pinfunction "GND3_5") (pintype "bidirectional"))
      (node (ref "U$10") (pin "3") (pinfunction "GND_3") (pintype "bidirectional"))
      (node (ref "U$10") (pin "7") (pinfunction "A0_7") (pintype "bidirectional"))
      (node (ref "U$10") (pin "8") (pinfunction "A1_8") (pintype "bidirectional"))
      (node (ref "U$11") (pin "1") (pinfunction "GND_1") (pintype "bidirectional"))
      (node (ref "U$12") (pin "1") (pinfunction "GND_1") (pintype "bidirectional"))
      (node (ref "U$13") (pin "A1") (pinfunction "A1_GND_A1") (pintype "bidirectional"))
      (node (ref "U$13") (pin "A12") (pinfunction "A12_GND_A12") (pintype "bidirectional"))
      (node (ref "U$13") (pin "B1") (pinfunction "B1_GND_B1") (pintype "bidirectional"))
      (node (ref "U$13") (pin "B12") (pinfunction "B12_GND_B12") (pintype "bidirectional"))
      (node (ref "U$13") (pin "P$1") (pinfunction "SHIELD_P$1") (pintype "bidirectional"))
      (node (ref "U$13") (pin "P$2") (pinfunction "SHIELD_P$2") (pintype "bidirectional"))
      (node (ref "U$13") (pin "P$3") (pinfunction "SHIELD_P$3") (pintype "bidirectional"))
      (node (ref "U$13") (pin "P$4") (pinfunction "SHIELD_P$4") (pintype "bidirectional"))
      (node (ref "U$14") (pin "P$1") (pinfunction "GND_P$1") (pintype "bidirectional"))
      (node (ref "U$15") (pin "P$1") (pinfunction "GND_P$1") (pintype "bidirectional"))
      (node (ref "U$3") (pin "10") (pinfunction "GND_10") (pintype "bidirectional"))
      (node (ref "U$3") (pin "12") (pinfunction "ADDR0_12") (pintype "bidirectional"))
      (node (ref "U$3") (pin "13") (pinfunction "ADDR1_13") (pintype "bidirectional"))
      (node (ref "U$3") (pin "22") (pinfunction "VSYS_22") (pintype "bidirectional"))
      (node (ref "U$3") (pin "3") (pinfunction "VCONN_3") (pintype "bidirectional"))
      (node (ref "U$3") (pin "EXP") (pinfunction "PAD_EXP") (pintype "bidirectional"))
      (node (ref "U$7") (pin "3") (pinfunction "GND_3") (pintype "bidirectional"))
      (node (ref "U$7") (pin "8") (pinfunction "A1_8") (pintype "bidirectional"))
      (node (ref "U$8") (pin "23") (pinfunction "VSS_1(P23)_23") (pintype "bidirectional"))
      (node (ref "U$8") (pin "35") (pinfunction "VSS_2(P35)_35") (pintype "bidirectional"))
      (node (ref "U$8") (pin "47") (pinfunction "VSS_3(P47)_47") (pintype "bidirectional"))
      (node (ref "U$8") (pin "8") (pinfunction "VSSA(P8)_8") (pintype "bidirectional"))
      (node (ref "U$8") (pin "_") (pinfunction "PAD_GND__") (pintype "bidirectional"))
      (node (ref "U$9") (pin "3") (pinfunction "GND_3") (pintype "bidirectional"))
    )
    (net (code "9") (name "KEY") (class "Default")
      (node (ref "C18") (pin "2") (pinfunction "2_2") (pintype "passive"))
      (node (ref "R35") (pin "1") (pinfunction "1_1") (pintype "passive"))
      (node (ref "SW1") (pin "B") (pinfunction "S_B") (pintype "passive"))
      (node (ref "SW1") (pin "B'") (pinfunction "S1_B'") (pintype "passive"))
      (node (ref "U$8") (pin "13") (pinfunction "PA3/ADC_IN3/COMP2_INP/USART2_RX_13") (pintype "bidirectional"))
    )
    (net (code "10") (name "NRST") (class "Default")
      (node (ref "J1") (pin "2") (pinfunction "2_2") (pintype "passive"))
      (node (ref "R1") (pin "1") (pinfunction "1_1") (pintype "passive"))
      (node (ref "U$8") (pin "7") (pinfunction "NRST(P7)_7") (pintype "bidirectional"))
    )
    (net (code "11") (name "Net-(C9-Pad1)") (class "Default")
      (node (ref "C9") (pin "1") (pinfunction "1_1") (pintype "passive"))
      (node (ref "R11") (pin "2") (pinfunction "2_2") (pintype "passive"))
    )
    (net (code "12") (name "Net-(C12-Pad1)") (class "Default")
      (node (ref "C12") (pin "1") (pinfunction "1_1") (pintype "passive"))
      (node (ref "R23") (pin "2") (pinfunction "2_2") (pintype "passive"))
    )
    (net (code "13") (name "Net-(C30-Pad1)") (class "Default")
      (node (ref "C30") (pin "1") (pinfunction "1_1") (pintype "passive"))
      (node (ref "R43") (pin "1") (pinfunction "1_1") (pintype "passive"))
    )
    (net (code "14") (name "Net-(ESDA25W1-CC1)") (class "Default")
      (node (ref "ESDA25W1") (pin "3") (pinfunction "CC1_3") (pintype "bidirectional"))
      (node (ref "U$13") (pin "A5") (pinfunction "A5_CC1_A5") (pintype "bidirectional"))
      (node (ref "U$3") (pin "1") (pinfunction "CC1DB_1") (pintype "bidirectional"))
      (node (ref "U$3") (pin "2") (pinfunction "CC1_2") (pintype "bidirectional"))
    )
    (net (code "15") (name "Net-(ESDA25W1-CC2)") (class "Default")
      (node (ref "ESDA25W1") (pin "2") (pinfunction "CC2_2") (pintype "bidirectional"))
      (node (ref "U$13") (pin "B5") (pinfunction "B5_CC2_B5") (pintype "bidirectional"))
      (node (ref "U$3") (pin "4") (pinfunction "CC2_4") (pintype "bidirectional"))
      (node (ref "U$3") (pin "5") (pinfunction "CC2DB_5") (pintype "bidirectional"))
    )
    (net (code "16") (name "Net-(LCD2-C1+)") (class "Default")
      (node (ref "C23") (pin "2") (pinfunction "2_2") (pintype "passive"))
      (node (ref "LCD2") (pin "3") (pinfunction "C1+_3") (pintype "bidirectional"))
    )
    (net (code "17") (name "Net-(LCD2-C1-)") (class "Default")
      (node (ref "C23") (pin "1") (pinfunction "1_1") (pintype "passive"))
      (node (ref "LCD2") (pin "4") (pinfunction "C1-_4") (pintype "bidirectional"))
    )
    (net (code "18") (name "Net-(LCD2-C2+)") (class "Default")
      (node (ref "C24") (pin "2") (pinfunction "2_2") (pintype "passive"))
      (node (ref "LCD2") (pin "1") (pinfunction "C2+_1") (pintype "bidirectional"))
    )
    (net (code "19") (name "Net-(LCD2-C2-)") (class "Default")
      (node (ref "C24") (pin "1") (pinfunction "1_1") (pintype "passive"))
      (node (ref "LCD2") (pin "2") (pinfunction "C2-_2") (pintype "bidirectional"))
    )
    (net (code "20") (name "Net-(LCD2-IREF)") (class "Default")
      (node (ref "LCD2") (pin "12") (pinfunction "IREF_12") (pintype "bidirectional"))
      (node (ref "R30") (pin "2") (pinfunction "2_2") (pintype "passive"))
    )
    (net (code "21") (name "Net-(LCD2-VCC)") (class "Default")
      (node (ref "C20") (pin "2") (pinfunction "2_2") (pintype "passive"))
      (node (ref "LCD2") (pin "14") (pinfunction "VCC_14") (pintype "power_in"))
    )
    (net (code "22") (name "Net-(LCD2-VCOMH)") (class "Default")
      (node (ref "C21") (pin "2") (pinfunction "2_2") (pintype "passive"))
      (node (ref "LCD2") (pin "13") (pinfunction "VCOMH_13") (pintype "power_in"))
    )
    (net (code "23") (name "Net-(T1-B)") (class "Default")
      (node (ref "R2") (pin "1") (pinfunction "1_1") (pintype "passive"))
      (node (ref "T1") (pin "1") (pinfunction "B_1") (pintype "passive"))
    )
    (net (code "24") (name "Net-(T1-C)") (class "Default")
      (node (ref "C3") (pin "2") (pinfunction "2_2") (pintype "passive"))
      (node (ref "R26") (pin "1") (pinfunction "1_1") (pintype "passive"))
      (node (ref "R27") (pin "2") (pinfunction "2_2") (pintype "passive"))
      (node (ref "T1") (pin "3") (pinfunction "C_3") (pintype "passive"))
      (node (ref "U$12") (pin "5") (pinfunction "EN_5") (pintype "bidirectional"))
    )
    (net (code "25") (name "Net-(T2-B)") (class "Default")
      (node (ref "R3") (pin "1") (pinfunction "1_1") (pintype "passive"))
      (node (ref "T2") (pin "1") (pinfunction "B_1") (pintype "passive"))
    )
    (net (code "26") (name "Net-(T2-C)") (class "Default")
      (node (ref "C2") (pin "2") (pinfunction "2_2") (pintype "passive"))
      (node (ref "R16") (pin "1") (pinfunction "1_1") (pintype "passive"))
      (node (ref "R22") (pin "2") (pinfunction "2_2") (pintype "passive"))
      (node (ref "T2") (pin "3") (pinfunction "C_3") (pintype "passive"))
      (node (ref "U$11") (pin "5") (pinfunction "EN_5") (pintype "bidirectional"))
    )
    (net (code "27") (name "Net-(U$1-OUT)") (class "Default")
      (node (ref "C1") (pin "2") (pinfunction "2_2") (pintype "passive"))
      (node (ref "D5") (pin "A") (pinfunction "A_A") (pintype "passive"))
      (node (ref "U$1") (pin "3") (pinfunction "OUT_3") (pintype "bidirectional"))
    )
    (net (code "28") (name "Net-(U$3-DISCH)") (class "Default")
      (node (ref "R45") (pin "2") (pinfunction "2_2") (pintype "passive"))
      (node (ref "U$3") (pin "9") (pinfunction "DISCH_9") (pintype "bidirectional"))
    )
    (net (code "29") (name "Net-(U$3-VBUS_EN_SNK)") (class "Default")
      (node (ref "R42") (pin "1") (pinfunction "1_1") (pintype "passive"))
      (node (ref "U$3") (pin "16") (pinfunction "VBUS_EN_SNK_16") (pintype "bidirectional"))
    )
    (net (code "30") (name "Net-(U$3-VBUS_VS_DISCH)") (class "Default")
      (node (ref "R44") (pin "2") (pinfunction "2_2") (pintype "passive"))
      (node (ref "U$3") (pin "18") (pinfunction "VBUS_VS_DISCH_18") (pintype "bidirectional"))
    )
    (net (code "31") (name "Net-(U$3-VREG_1V2)") (class "Default")
      (node (ref "C29") (pin "1") (pinfunction "1_1") (pintype "passive"))
      (node (ref "U$3") (pin "21") (pinfunction "VREG_1V2_21") (pintype "bidirectional"))
    )
    (net (code "32") (name "Net-(U$3-VREG_2V7)") (class "Default")
      (node (ref "C28") (pin "1") (pinfunction "1_1") (pintype "passive"))
      (node (ref "U$3") (pin "23") (pinfunction "VREG_2V7_23") (pintype "bidirectional"))
    )
    (net (code "33") (name "Net-(U$8-BOOT0(P44))") (class "Default")
      (node (ref "R39") (pin "2") (pinfunction "2_2") (pintype "passive"))
      (node (ref "R40") (pin "1") (pinfunction "1_1") (pintype "passive"))
      (node (ref "U$8") (pin "44") (pinfunction "BOOT0(P44)_44") (pintype "bidirectional"))
    )
    (net (code "34") (name "Net-(U$11-BOOT)") (class "Default")
      (node (ref "R11") (pin "1") (pinfunction "1_1") (pintype "passive"))
      (node (ref "U$11") (pin "6") (pinfunction "BOOT_6") (pintype "bidirectional"))
    )
    (net (code "35") (name "Net-(U$11-FB)") (class "Default")
      (node (ref "R12") (pin "1") (pinfunction "1_1") (pintype "passive"))
      (node (ref "R15") (pin "2") (pinfunction "2_2") (pintype "passive"))
      (node (ref "U$11") (pin "4") (pinfunction "FB_4") (pintype "bidirectional"))
    )
    (net (code "36") (name "Net-(U$11-SW)") (class "Default")
      (node (ref "C9") (pin "2") (pinfunction "2_2") (pintype "passive"))
      (node (ref "L1") (pin "1") (pinfunction "1_1") (pintype "passive"))
      (node (ref "U$11") (pin "2") (pinfunction "SW_2") (pintype "bidirectional"))
    )
    (net (code "37") (name "Net-(U$12-BOOT)") (class "Default")
      (node (ref "R23") (pin "1") (pinfunction "1_1") (pintype "passive"))
      (node (ref "U$12") (pin "6") (pinfunction "BOOT_6") (pintype "bidirectional"))
    )
    (net (code "38") (name "Net-(U$12-FB)") (class "Default")
      (node (ref "R24") (pin "1") (pinfunction "1_1") (pintype "passive"))
      (node (ref "R25") (pin "2") (pinfunction "2_2") (pintype "passive"))
      (node (ref "U$12") (pin "4") (pinfunction "FB_4") (pintype "bidirectional"))
    )
    (net (code "39") (name "Net-(U$12-SW)") (class "Default")
      (node (ref "C12") (pin "2") (pinfunction "2_2") (pintype "passive"))
      (node (ref "L2") (pin "1") (pinfunction "1_1") (pintype "passive"))
      (node (ref "U$12") (pin "2") (pinfunction "SW_2") (pintype "bidirectional"))
    )
    (net (code "40") (name "Net-(U$16-G)") (class "Default")
      (node (ref "R41") (pin "1") (pinfunction "1_1") (pintype "passive"))
      (node (ref "R42") (pin "2") (pinfunction "2_2") (pintype "passive"))
      (node (ref "R43") (pin "2") (pinfunction "2_2") (pintype "passive"))
      (node (ref "U$16") (pin "P$4") (pinfunction "G_P$4") (pintype "bidirectional"))
    )
    (net (code "41") (name "OLED_RST") (class "Default")
      (node (ref "C4") (pin "2") (pinfunction "2_2") (pintype "passive"))
      (node (ref "D2") (pin "A") (pinfunction "A_A") (pintype "passive"))
      (node (ref "LCD2") (pin "9") (pinfunction "RES#_9") (pintype "bidirectional"))
      (node (ref "R31") (pin "1") (pinfunction "1_1") (pintype "passive"))
    )
    (net (code "42") (name "SCL") (class "Default")
      (node (ref "J11") (pin "2") (pinfunction "2_2") (pintype "passive"))
      (node (ref "R37") (pin "1") (pinfunction "1_1") (pintype "passive"))
      (node (ref "U$3") (pin "7") (pinfunction "SCL_7") (pintype "bidirectional"))
      (node (ref "U$8") (pin "42") (pinfunction "PB6USART1_TX/I2C1_SCL_42") (pintype "bidirectional"))
    )
    (net (code "43") (name "SCL_2") (class "Default")
      (node (ref "LCD2") (pin "10") (pinfunction "SCL_10") (pintype "bidirectional"))
      (node (ref "R33") (pin "1") (pinfunction "1_1") (pintype "passive"))
      (node (ref "U$10") (pin "5") (pinfunction "SCL_5") (pintype "bidirectional"))
      (node (ref "U$7") (pin "5") (pinfunction "SCL_5") (pintype "bidirectional"))
      (node (ref "U$8") (pin "21") (pinfunction "PB10/I2C2_SCL/TIM2_CH3/USART3_TX_21") (pintype "bidirectional"))
      (node (ref "U$9") (pin "5") (pinfunction "SCL_5") (pintype "bidirectional"))
    )
    (net (code "44") (name "SDA") (class "Default")
      (node (ref "J11") (pin "3") (pinfunction "3_3") (pintype "passive"))
      (node (ref "R38") (pin "1") (pinfunction "1_1") (pintype "passive"))
      (node (ref "U$3") (pin "8") (pinfunction "SDA_8") (pintype "bidirectional"))
      (node (ref "U$8") (pin "43") (pinfunction "PB7/USART1_RX/I2C1_SDA_43") (pintype "bidirectional"))
    )
    (net (code "45") (name "SDA_2") (class "Default")
      (node (ref "LCD2") (pin "11") (pinfunction "SDA_11") (pintype "bidirectional"))
      (node (ref "R34") (pin "1") (pinfunction "1_1") (pintype "passive"))
      (node (ref "U$10") (pin "6") (pinfunction "SDA_6") (pintype "bidirectional"))
      (node (ref "U$7") (pin "6") (pinfunction "SDA_6") (pintype "bidirectional"))
      (node (ref "U$8") (pin "22") (pinfunction "PB11/I2C2_SDA/TIM2_C4/USART3_RX_22") (pintype "bidirectional"))
      (node (ref "U$9") (pin "6") (pinfunction "SDA_6") (pintype "bidirectional"))
    )
    (net (code "46") (name "STM_USB_D+") (class "Default")
      (node (ref "R29") (pin "1") (pinfunction "1_1") (pintype "passive"))
      (node (ref "U$8") (pin "33") (pinfunction "PA12/USB_DP/CAN_TX_33") (pintype "bidirectional"))
    )
    (net (code "47") (name "STM_USB_D-") (class "Default")
      (node (ref "R28") (pin "1") (pinfunction "1_1") (pintype "passive"))
      (node (ref "U$8") (pin "32") (pinfunction "PA11/USB_DM/CAN_RX_32") (pintype "bidirectional"))
    )
    (net (code "48") (name "STUSB_AB") (class "Default")
      (node (ref "J13") (pin "2") (pinfunction "2_2") (pintype "passive"))
      (node (ref "U$3") (pin "17") (pinfunction "A-B_SIDE_17") (pintype "bidirectional"))
      (node (ref "U$8") (pin "28") (pinfunction "PB15/WKUP7/RTC_REFIN/SPI2_MOSI_28") (pintype "bidirectional"))
    )
    (net (code "49") (name "STUSB_ALERT") (class "Default")
      (node (ref "J11") (pin "5") (pinfunction "5_5") (pintype "passive"))
      (node (ref "U$3") (pin "19") (pinfunction "ALERT_19") (pintype "bidirectional"))
      (node (ref "U$8") (pin "29") (pinfunction "PA8/TIM1_CH1_29") (pintype "bidirectional"))
    )
    (net (code "50") (name "STUSB_ATTACH") (class "Default")
      (node (ref "J11") (pin "4") (pinfunction "4_4") (pintype "passive"))
      (node (ref "U$3") (pin "11") (pinfunction "ATTACH_11") (pintype "bidirectional"))
      (node (ref "U$8") (pin "30") (pinfunction "PA9/USART1_TX/TIM1_CH2_30") (pintype "bidirectional"))
    )
    (net (code "51") (name "STUSB_GPIO") (class "Default")
      (node (ref "J13") (pin "1") (pinfunction "1_1") (pintype "passive"))
      (node (ref "U$3") (pin "15") (pinfunction "GPIO_15") (pintype "bidirectional"))
    )
    (net (code "52") (name "STUSB_RST") (class "Default")
      (node (ref "J11") (pin "1") (pinfunction "1_1") (pintype "passive"))
      (node (ref "R32") (pin "2") (pinfunction "2_2") (pintype "passive"))
      (node (ref "U$3") (pin "6") (pinfunction "RESET_6") (pintype "bidirectional"))
      (node (ref "U$8") (pin "31") (pinfunction "PA10/USART1_RX/TIM1_CH3_31") (pintype "bidirectional"))
    )
    (net (code "53") (name "SWCLK") (class "Default")
      (node (ref "J1") (pin "3") (pinfunction "3_3") (pintype "passive"))
      (node (ref "U$8") (pin "37") (pinfunction "PA14/USART2_TX/SWCLK_37") (pintype "bidirectional"))
    )
    (net (code "54") (name "SWDIO") (class "Default")
      (node (ref "J1") (pin "4") (pinfunction "4_4") (pintype "passive"))
      (node (ref "U$8") (pin "34") (pinfunction "PA13/SWDIO_34") (pintype "bidirectional"))
    )
    (net (code "55") (name "UART_RX") (class "Default")
      (node (ref "J9") (pin "1") (pinfunction "1_1") (pintype "passive"))
      (node (ref "U$8") (pin "11") (pinfunction "PA1/ADC_IN1/COMP1_INP/USART4_RX_11") (pintype "bidirectional"))
    )
    (net (code "56") (name "UART_TX") (class "Default")
      (node (ref "J9") (pin "2") (pinfunction "2_2") (pintype "passive"))
      (node (ref "U$8") (pin "10") (pinfunction "PA0/USART4_TX/WKUP1/ADC_IN0_10") (pintype "bidirectional"))
    )
    (net (code "57") (name "USB-PD_VDD_OUT") (class "Default")
      (node (ref "C27") (pin "1") (pinfunction "1_1") (pintype "passive"))
      (node (ref "D1") (pin "C") (pinfunction "C_C") (pintype "passive"))
      (node (ref "J4") (pin "2") (pinfunction "2_2") (pintype "bidirectional"))
      (node (ref "J4") (pin "4") (pinfunction "4_4") (pintype "bidirectional"))
      (node (ref "J4") (pin "6") (pinfunction "6_6") (pintype "bidirectional"))
      (node (ref "R19") (pin "1") (pinfunction "1_1") (pintype "passive"))
      (node (ref "U$10") (pin "2") (pinfunction "IN-_2") (pintype "bidirectional"))
    )
    (net (code "58") (name "USB_D+") (class "Default")
      (node (ref "J12") (pin "1") (pinfunction "1_1") (pintype "passive"))
      (node (ref "R29") (pin "2") (pinfunction "2_2") (pintype "passive"))
      (node (ref "R55") (pin "1") (pinfunction "1_1") (pintype "passive"))
      (node (ref "U$13") (pin "A6") (pinfunction "A6_D+_A6") (pintype "bidirectional"))
      (node (ref "U$13") (pin "B6") (pinfunction "B6_D+_B6") (pintype "bidirectional"))
    )
    (net (code "59") (name "USB_D-") (class "Default")
      (node (ref "J12") (pin "2") (pinfunction "2_2") (pintype "passive"))
      (node (ref "R28") (pin "2") (pinfunction "2_2") (pintype "passive"))
      (node (ref "U$13") (pin "A7") (pinfunction "A7_D-_A7") (pintype "bidirectional"))
      (node (ref "U$13") (pin "B7") (pinfunction "B7_D-_B7") (pintype "bidirectional"))
    )
    (net (code "60") (name "USB_PD_VDD") (class "Default")
      (node (ref "C11") (pin "2") (pinfunction "2_2") (pintype "passive"))
      (node (ref "C14") (pin "2") (pinfunction "2_2") (pintype "passive"))
      (node (ref "C30") (pin "2") (pinfunction "2_2") (pintype "passive"))
      (node (ref "C32") (pin "1") (pinfunction "1_1") (pintype "passive"))
      (node (ref "J10") (pin "1") (pinfunction "1_1") (pintype "passive"))
      (node (ref "R16") (pin "2") (pinfunction "2_2") (pintype "passive"))
      (node (ref "R19") (pin "2") (pinfunction "2_2") (pintype "passive"))
      (node (ref "R26") (pin "2") (pinfunction "2_2") (pintype "passive"))
      (node (ref "R45") (pin "1") (pinfunction "1_1") (pintype "passive"))
      (node (ref "U$10") (pin "1") (pinfunction "IN+_1") (pintype "bidirectional"))
      (node (ref "U$11") (pin "3") (pinfunction "VIN_3") (pintype "bidirectional"))
      (node (ref "U$12") (pin "3") (pinfunction "VIN_3") (pintype "bidirectional"))
      (node (ref "U$15") (pin "P$2") (pinfunction "VBUS_P$2") (pintype "bidirectional"))
      (node (ref "U$16") (pin "P$5") (pinfunction "D_P$5") (pintype "bidirectional"))
      (node (ref "U$16") (pin "P$6") (pinfunction "D_P$6") (pintype "bidirectional"))
      (node (ref "U$16") (pin "P$7") (pinfunction "D_P$7") (pintype "bidirectional"))
      (node (ref "U$16") (pin "P$8") (pinfunction "D_P$8") (pintype "bidirectional"))
      (node (ref "U$16") (pin "P$9") (pinfunction "D_P$9") (pintype "bidirectional"))
    )
    (net (code "61") (name "USB_PD_VDD*") (class "Default")
      (node (ref "C31") (pin "1") (pinfunction "1_1") (pintype "passive"))
      (node (ref "R41") (pin "2") (pinfunction "2_2") (pintype "passive"))
      (node (ref "R44") (pin "1") (pinfunction "1_1") (pintype "passive"))
      (node (ref "U$1") (pin "2") (pinfunction "IN_2") (pintype "bidirectional"))
      (node (ref "U$13") (pin "A4") (pinfunction "A4_VBUS_A4") (pintype "bidirectional"))
      (node (ref "U$13") (pin "A9") (pinfunction "A9_VBUS_A9") (pintype "bidirectional"))
      (node (ref "U$13") (pin "B4") (pinfunction "B4_VBUS_B4") (pintype "bidirectional"))
      (node (ref "U$13") (pin "B9") (pinfunction "B_VBUS_B9") (pintype "bidirectional"))
      (node (ref "U$14") (pin "P$2") (pinfunction "VBUS_P$2") (pintype "bidirectional"))
      (node (ref "U$16") (pin "P$1") (pinfunction "S_P$1") (pintype "bidirectional"))
      (node (ref "U$16") (pin "P$2") (pinfunction "S_P$2") (pintype "bidirectional"))
      (node (ref "U$16") (pin "P$3") (pinfunction "S_P$3") (pintype "bidirectional"))
      (node (ref "U$3") (pin "24") (pinfunction "VDD_24") (pintype "bidirectional"))
    )
    (net (code "62") (name "VBREF") (class "Default")
      (node (ref "LCD2") (pin "6") (pinfunction "VBREF_6") (pintype "power_in"))
    )
    (net (code "63") (name "unconnected-(U$3-PDO2-Pad20)") (class "Default")
      (node (ref "U$3") (pin "20") (pinfunction "PDO2_20") (pintype "bidirectional"))
    )
    (net (code "64") (name "unconnected-(U$3-PDO3-Pad14)") (class "Default")
      (node (ref "U$3") (pin "14") (pinfunction "PDO3_14") (pintype "bidirectional"))
    )
    (net (code "65") (name "unconnected-(U$8-PA2{slash}ADC_IN2{slash}WKUP4USART2_TX-Pad12)") (class "Default")
      (node (ref "U$8") (pin "12") (pinfunction "PA2/ADC_IN2/WKUP4USART2_TX_12") (pintype "bidirectional"))
    )
    (net (code "66") (name "unconnected-(U$8-PA4{slash}ADC_IN4{slash}DAC_OUT1-Pad14)") (class "Default")
      (node (ref "U$8") (pin "14") (pinfunction "PA4/ADC_IN4/DAC_OUT1_14") (pintype "bidirectional"))
    )
    (net (code "67") (name "unconnected-(U$8-PA5{slash}ADC_IN5{slash}DAC_OUT2{slash}SPI1_SCK-Pad15)") (class "Default")
      (node (ref "U$8") (pin "15") (pinfunction "PA5/ADC_IN5/DAC_OUT2/SPI1_SCK_15") (pintype "bidirectional"))
    )
    (net (code "68") (name "unconnected-(U$8-PA6{slash}ADC_IN6{slash}SPI1_MISO{slash}TIM3_CH1-Pad16)") (class "Default")
      (node (ref "U$8") (pin "16") (pinfunction "PA6/ADC_IN6/SPI1_MISO/TIM3_CH1_16") (pintype "bidirectional"))
    )
    (net (code "69") (name "unconnected-(U$8-PA7{slash}ADC_IN7{slash}SPI1_MOSI{slash}TIM3_CH2-Pad17)") (class "Default")
      (node (ref "U$8") (pin "17") (pinfunction "PA7/ADC_IN7/SPI1_MOSI/TIM3_CH2_17") (pintype "bidirectional"))
    )
    (net (code "70") (name "unconnected-(U$8-PA15{slash}USART2_RX-Pad38)") (class "Default")
      (node (ref "U$8") (pin "38") (pinfunction "PA15/USART2_RX_38") (pintype "bidirectional"))
    )
    (net (code "71") (name "unconnected-(U$8-PB0{slash}ADC_IN8{slash}TIM3_CH3-Pad18)") (class "Default")
      (node (ref "U$8") (pin "18") (pinfunction "PB0/ADC_IN8/TIM3_CH3_18") (pintype "bidirectional"))
    )
    (net (code "72") (name "unconnected-(U$8-PB1{slash}ADC_IN9{slash}TIM3_CH4-Pad19)") (class "Default")
      (node (ref "U$8") (pin "19") (pinfunction "PB1/ADC_IN9/TIM3_CH4_19") (pintype "bidirectional"))
    )
    (net (code "73") (name "unconnected-(U$8-PB2-Pad20)") (class "Default")
      (node (ref "U$8") (pin "20") (pinfunction "PB2_20") (pintype "bidirectional"))
    )
    (net (code "74") (name "unconnected-(U$8-PB5{slash}WKUP6{slash}SPI1_MOSI{slash}TIM3_CH2-Pad41)") (class "Default")
      (node (ref "U$8") (pin "41") (pinfunction "PB5/WKUP6/SPI1_MOSI/TIM3_CH2_41") (pintype "bidirectional"))
    )
    (net (code "75") (name "unconnected-(U$8-PB8{slash}I2C1_SCL{slash}TIM16_CH1{slash}CAN_RX-Pad45)") (class "Default")
      (node (ref "U$8") (pin "45") (pinfunction "PB8/I2C1_SCL/TIM16_CH1/CAN_RX_45") (pintype "bidirectional"))
    )
    (net (code "76") (name "unconnected-(U$8-PB9{slash}I2C1_SDA{slash}TIM17_CH1{slash}CAN_TX-Pad46)") (class "Default")
      (node (ref "U$8") (pin "46") (pinfunction "PB9/I2C1_SDA/TIM17_CH1/CAN_TX_46") (pintype "bidirectional"))
    )
    (net (code "77") (name "unconnected-(U$8-PB12-Pad25)") (class "Default")
      (node (ref "U$8") (pin "25") (pinfunction "PB12_25") (pintype "bidirectional"))
    )
    (net (code "78") (name "unconnected-(U$8-PB13{slash}SPI2_SCK{slash}I2C2_SCL-Pad26)") (class "Default")
      (node (ref "U$8") (pin "26") (pinfunction "PB13/SPI2_SCK/I2C2_SCL_26") (pintype "bidirectional"))
    )
    (net (code "79") (name "unconnected-(U$8-PB14{slash}SPI2_MISO{slash}I2C2_SDA-Pad27)") (class "Default")
      (node (ref "U$8") (pin "27") (pinfunction "PB14/SPI2_MISO/I2C2_SDA_27") (pintype "bidirectional"))
    )
    (net (code "80") (name "unconnected-(U$8-PC13{slash}WKUP2{slash}RTC_TAMP1{slash}RTC_TS{slash}RTC_OUT-Pad2)") (class "Default")
      (node (ref "U$8") (pin "2") (pinfunction "PC13/WKUP2/RTC_TAMP1/RTC_TS/RTC_OUT_2") (pintype "bidirectional"))
    )
    (net (code "81") (name "unconnected-(U$8-PC14{slash}OSC32_IN-Pad3)") (class "Default")
      (node (ref "U$8") (pin "3") (pinfunction "PC14/OSC32_IN_3") (pintype "bidirectional"))
    )
    (net (code "82") (name "unconnected-(U$8-PC15{slash}OSC32_OUT-Pad4)") (class "Default")
      (node (ref "U$8") (pin "4") (pinfunction "PC15/OSC32_OUT_4") (pintype "bidirectional"))
    )
    (net (code "83") (name "unconnected-(U$8-PF0{slash}OSC_IN-Pad5)") (class "Default")
      (node (ref "U$8") (pin "5") (pinfunction "PF0/OSC_IN_5") (pintype "bidirectional"))
    )
    (net (code "84") (name "unconnected-(U$8-PF1{slash}OSC_OUT-Pad6)") (class "Default")
      (node (ref "U$8") (pin "6") (pinfunction "PF1/OSC_OUT_6") (pintype "bidirectional"))
    )
    (net (code "85") (name "unconnected-(U$13-A8_SBU1-PadA8)") (class "Default")
      (node (ref "U$13") (pin "A8") (pinfunction "A8_SBU1_A8") (pintype "bidirectional"))
    )
    (net (code "86") (name "unconnected-(U$13-B8_SBU2-PadB8)") (class "Default")
      (node (ref "U$13") (pin "B8") (pinfunction "B8_SBU2_B8") (pintype "bidirectional"))
    )
  )
)
